# SHT21_breakout.net
KiCad netlist of a schematic drawn in EAGLE
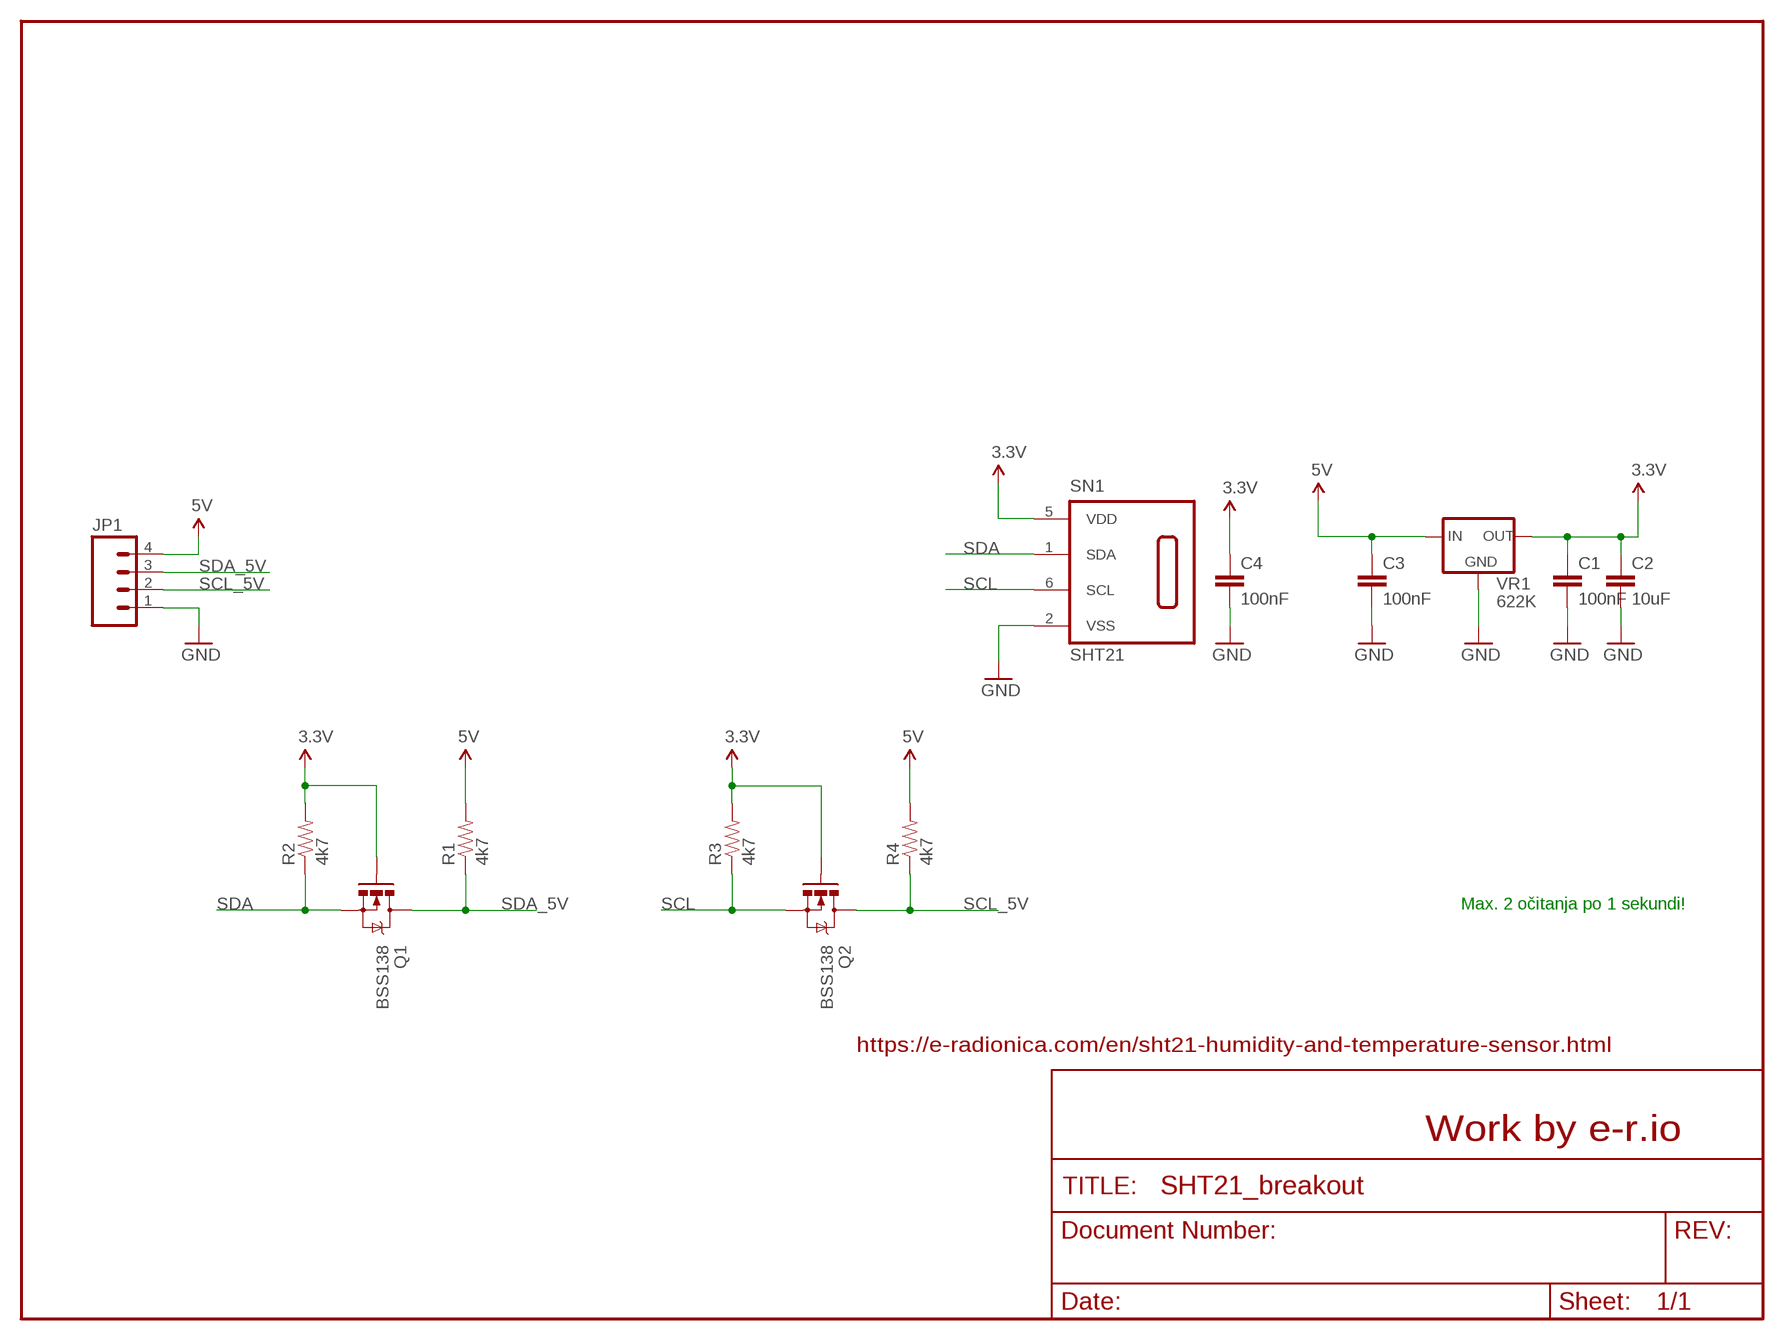
[diagram p0: schematic, sheet 1]

(export (version "E")
  (design (tool "Eeschema 10.0.6"))
  (components
    (comp (ref "C1")
      (value "100nF")
      (footprint "eagle-import:0603-CAP")
      (libsource (lib "eagle-import") (part "CAP0603-CAP"))
    )
    (comp (ref "C2")
      (value "10uF")
      (footprint "eagle-import:1206")
      (libsource (lib "eagle-import") (part "CAP1206"))
    )
    (comp (ref "C3")
      (value "100nF")
      (footprint "eagle-import:0603-CAP")
      (libsource (lib "eagle-import") (part "CAP0603-CAP"))
    )
    (comp (ref "C4")
      (value "100nF")
      (footprint "eagle-import:0603-CAP")
      (libsource (lib "eagle-import") (part "CAP0603-CAP"))
    )
    (comp (ref "JP1")
      (value "M04PTH")
      (footprint "eagle-import:1X04")
      (libsource (lib "eagle-import") (part "M04PTH"))
    )
    (comp (ref "Q1")
      (value "BSS138")
      (footprint "eagle-import:SOT23-3")
      (libsource (lib "eagle-import") (part "MOSFET-NCHANNELSMD"))
    )
    (comp (ref "Q2")
      (value "BSS138")
      (footprint "eagle-import:SOT23-3")
      (libsource (lib "eagle-import") (part "MOSFET-NCHANNELSMD"))
    )
    (comp (ref "R1")
      (value "4k7")
      (footprint "eagle-import:0603-RES")
      (libsource (lib "eagle-import") (part "RESISTOR0603-RES"))
    )
    (comp (ref "R2")
      (value "4k7")
      (footprint "eagle-import:0603-RES")
      (libsource (lib "eagle-import") (part "RESISTOR0603-RES"))
    )
    (comp (ref "R3")
      (value "4k7")
      (footprint "eagle-import:0603-RES")
      (libsource (lib "eagle-import") (part "RESISTOR0603-RES"))
    )
    (comp (ref "R4")
      (value "4k7")
      (footprint "eagle-import:0603-RES")
      (libsource (lib "eagle-import") (part "RESISTOR0603-RES"))
    )
    (comp (ref "SN1")
      (value "SHT21")
      (footprint "eagle-import:DFN6_SHT")
      (libsource (lib "eagle-import") (part "SHT21"))
    )
    (comp (ref "VR1")
      (value "622K")
      (footprint "eagle-import:662K")
      (libsource (lib "eagle-import") (part "622K"))
    )
  )
  (nets
    (net (code "1") (name "/SCL") (class "Default")
      (node (ref "Q2") (pin "2") (pinfunction "S_2") (pintype "passive"))
      (node (ref "R3") (pin "1") (pinfunction "1_1") (pintype "passive"))
      (node (ref "SN1") (pin "6") (pinfunction "SCL_6") (pintype "bidirectional"))
    )
    (net (code "2") (name "/SCL_5V") (class "Default")
      (node (ref "JP1") (pin "2") (pinfunction "2_2") (pintype "passive"))
      (node (ref "Q2") (pin "3") (pinfunction "D_3") (pintype "passive"))
      (node (ref "R4") (pin "1") (pinfunction "1_1") (pintype "passive"))
    )
    (net (code "3") (name "/SDA") (class "Default")
      (node (ref "Q1") (pin "2") (pinfunction "S_2") (pintype "passive"))
      (node (ref "R2") (pin "1") (pinfunction "1_1") (pintype "passive"))
      (node (ref "SN1") (pin "1") (pinfunction "SDA_1") (pintype "bidirectional"))
    )
    (net (code "4") (name "/SDA_5V") (class "Default")
      (node (ref "JP1") (pin "3") (pinfunction "3_3") (pintype "passive"))
      (node (ref "Q1") (pin "3") (pinfunction "D_3") (pintype "passive"))
      (node (ref "R1") (pin "1") (pinfunction "1_1") (pintype "passive"))
    )
    (net (code "5") (name "3.3V") (class "Default")
      (node (ref "C1") (pin "1") (pinfunction "1_1") (pintype "passive"))
      (node (ref "C2") (pin "1") (pinfunction "1_1") (pintype "passive"))
      (node (ref "C4") (pin "1") (pinfunction "1_1") (pintype "passive"))
      (node (ref "Q1") (pin "1") (pinfunction "G_1") (pintype "passive"))
      (node (ref "Q2") (pin "1") (pinfunction "G_1") (pintype "passive"))
      (node (ref "R2") (pin "2") (pinfunction "2_2") (pintype "passive"))
      (node (ref "R3") (pin "2") (pinfunction "2_2") (pintype "passive"))
      (node (ref "SN1") (pin "5") (pinfunction "VDD_5") (pintype "power_in"))
      (node (ref "VR1") (pin "OUT") (pinfunction "OUT_OUT") (pintype "output"))
    )
    (net (code "6") (name "5V") (class "Default")
      (node (ref "C3") (pin "1") (pinfunction "1_1") (pintype "passive"))
      (node (ref "JP1") (pin "4") (pinfunction "4_4") (pintype "passive"))
      (node (ref "R1") (pin "2") (pinfunction "2_2") (pintype "passive"))
      (node (ref "R4") (pin "2") (pinfunction "2_2") (pintype "passive"))
      (node (ref "VR1") (pin "IN") (pinfunction "IN_IN") (pintype "input"))
    )
    (net (code "7") (name "GND") (class "Default")
      (node (ref "C1") (pin "2") (pinfunction "2_2") (pintype "passive"))
      (node (ref "C2") (pin "2") (pinfunction "2_2") (pintype "passive"))
      (node (ref "C3") (pin "2") (pinfunction "2_2") (pintype "passive"))
      (node (ref "C4") (pin "2") (pinfunction "2_2") (pintype "passive"))
      (node (ref "JP1") (pin "1") (pinfunction "1_1") (pintype "passive"))
      (node (ref "SN1") (pin "2") (pinfunction "VSS_2") (pintype "power_in"))
      (node (ref "VR1") (pin "GND") (pinfunction "GND_GND") (pintype "input"))
    )
  )
)
